# ControlCommande_Motors.net
KiCad netlist of a schematic drawn in Altium Designer
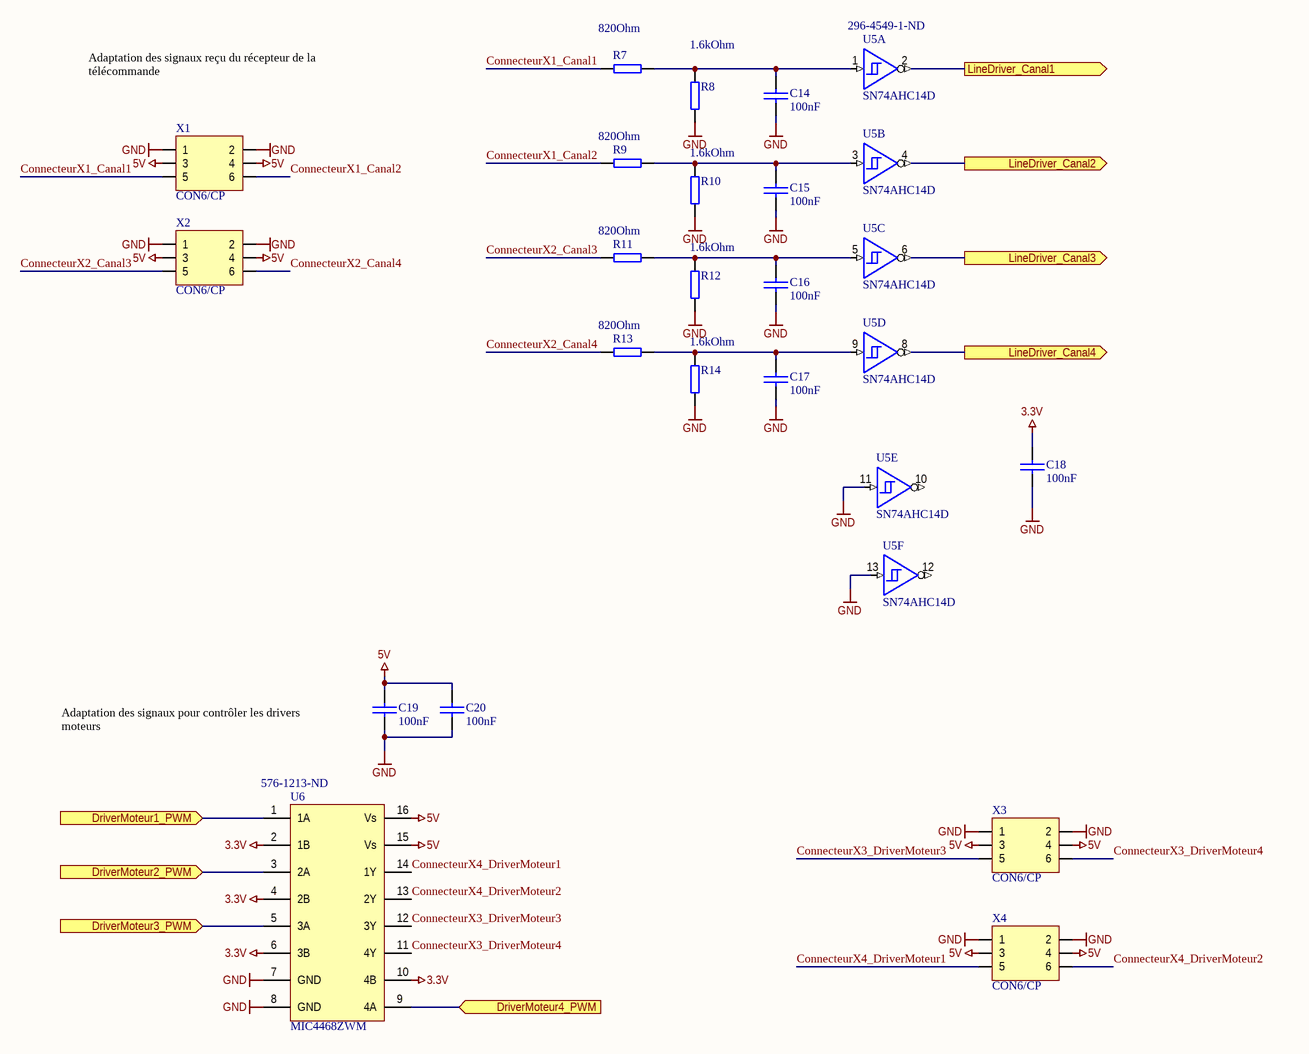
[diagram p0: ControlCommande&Motors.SchDoc]

(export (version "E")
  (design (tool "Eeschema 10.0.6"))
  (components
    (comp (ref "C14")
      (value "100nF")
      (footprint "060301")
      (description "CAPA")
      (fields (field (name "Comment") "GRM188R71E104KA01D"))
      (libsource (lib "General-Sch-205") (part "CAPA"))
    )
    (comp (ref "C15")
      (value "100nF")
      (footprint "060301")
      (description "CAPA")
      (fields (field (name "Comment") "GRM188R71E104KA01D"))
      (libsource (lib "General-Sch-205") (part "CAPA"))
    )
    (comp (ref "C16")
      (value "100nF")
      (footprint "060301")
      (description "CAPA")
      (fields (field (name "Comment") "GRM188R71E104KA01D"))
      (libsource (lib "General-Sch-205") (part "CAPA"))
    )
    (comp (ref "C17")
      (value "100nF")
      (footprint "060301")
      (description "CAPA")
      (fields (field (name "Comment") "GRM188R71E104KA01D"))
      (libsource (lib "General-Sch-205") (part "CAPA"))
    )
    (comp (ref "C18")
      (value "100nF")
      (footprint "060301")
      (description "CAPA")
      (fields (field (name "Comment") "GRM188R71E104KA01D"))
      (libsource (lib "General-Sch-205") (part "CAPA"))
    )
    (comp (ref "C19")
      (value "100nF")
      (footprint "060301")
      (description "CAPA")
      (fields (field (name "Comment") "GRM188R71E104KA01D"))
      (libsource (lib "General-Sch-205") (part "CAPA"))
    )
    (comp (ref "C20")
      (value "100nF")
      (footprint "060301")
      (description "CAPA")
      (fields (field (name "Comment") "GRM188R71E104KA01D"))
      (libsource (lib "General-Sch-205") (part "CAPA"))
    )
    (comp (ref "R7")
      (value "820Ohm")
      (footprint "080501")
      (fields (field (name "Comment") "RMCF0805JT820R"))
      (libsource (lib "General-Sch-205") (part "RES"))
    )
    (comp (ref "R8")
      (value "1.6kOhm")
      (footprint "080501")
      (fields (field (name "Comment") "ERJ-6GEYJ162V"))
      (libsource (lib "General-Sch-205") (part "RES"))
    )
    (comp (ref "R9")
      (value "820Ohm")
      (footprint "080501")
      (fields (field (name "Comment") "RMCF0805JT820R"))
      (libsource (lib "General-Sch-205") (part "RES"))
    )
    (comp (ref "R10")
      (value "1.6kOhm")
      (footprint "080501")
      (fields (field (name "Comment") "ERJ-6GEYJ162V"))
      (libsource (lib "General-Sch-205") (part "RES"))
    )
    (comp (ref "R11")
      (value "820Ohm")
      (footprint "080501")
      (fields (field (name "Comment") "RMCF0805JT820R"))
      (libsource (lib "General-Sch-205") (part "RES"))
    )
    (comp (ref "R12")
      (value "1.6kOhm")
      (footprint "080501")
      (fields (field (name "Comment") "ERJ-6GEYJ162V"))
      (libsource (lib "General-Sch-205") (part "RES"))
    )
    (comp (ref "R13")
      (value "820Ohm")
      (footprint "080501")
      (fields (field (name "Comment") "RMCF0805JT820R"))
      (libsource (lib "General-Sch-205") (part "RES"))
    )
    (comp (ref "R14")
      (value "1.6kOhm")
      (footprint "080501")
      (fields (field (name "Comment") "ERJ-6GEYJ162V"))
      (libsource (lib "General-Sch-205") (part "RES"))
    )
    (comp (ref "U5")
      (value "SN74AHC14D")
      (footprint "SO1401")
      (fields (field (name "SUPPLIER PART NUMBER 1") "296-4549-1-ND"))
      (libsource (lib "EISI") (part "SN74AHC14D"))
    )
    (comp (ref "U6")
      (value "MIC4468ZWM")
      (footprint "SOIC127P1030-16M")
      (fields (field (name "SUPPLIER PART NUMBER 1") "576-1213-ND"))
      (libsource (lib "Schlib1") (part "MIC4468"))
    )
    (comp (ref "X1")
      (value "CON6/CP")
      (footprint "J2X3_2.54")
      (description "Connecteur récepteur télécommande cannaux 1 & 2")
      (libsource (lib "General-Sch-205") (part "CON6/CP"))
    )
    (comp (ref "X2")
      (value "CON6/CP")
      (footprint "J2X3_2.54")
      (description "Connecteur récepteur télécommande cannaux 3 & 4")
      (libsource (lib "General-Sch-205") (part "CON6/CP"))
    )
    (comp (ref "X3")
      (value "CON6/CP")
      (footprint "J2X3_2.54")
      (description "Connecteur contrôleur moteurs 3 (arrière) & 4 (gauche)")
      (libsource (lib "General-Sch-205") (part "CON6/CP"))
    )
    (comp (ref "X4")
      (value "CON6/CP")
      (footprint "J2X3_2.54")
      (description "Connecteur contrôleur moteurs 1 (avant) & 2 (droite)")
      (libsource (lib "General-Sch-205") (part "CON6/CP"))
    )
  )
  (nets
    (net (code "1") (name "/ConnecteurX1_Canal1") (class "Default")
      (node (ref "R7") (pin "1") (pintype "passive"))
      (node (ref "X1") (pin "5") (pinfunction "5_5") (pintype "passive"))
    )
    (net (code "2") (name "/ConnecteurX1_Canal2") (class "Default")
      (node (ref "R9") (pin "1") (pintype "passive"))
      (node (ref "X1") (pin "6") (pinfunction "6_6") (pintype "passive"))
    )
    (net (code "3") (name "/ConnecteurX2_Canal3") (class "Default")
      (node (ref "R11") (pin "1") (pintype "passive"))
      (node (ref "X2") (pin "5") (pinfunction "5_5") (pintype "passive"))
    )
    (net (code "4") (name "/ConnecteurX2_Canal4") (class "Default")
      (node (ref "R13") (pin "1") (pintype "passive"))
      (node (ref "X2") (pin "6") (pinfunction "6_6") (pintype "passive"))
    )
    (net (code "5") (name "/ConnecteurX3_DriverMoteur3") (class "Default")
      (node (ref "U6") (pin "12") (pinfunction "3Y_12") (pintype "passive"))
      (node (ref "X3") (pin "5") (pinfunction "5_5") (pintype "passive"))
    )
    (net (code "6") (name "/ConnecteurX3_DriverMoteur4") (class "Default")
      (node (ref "U6") (pin "11") (pinfunction "4Y_11") (pintype "passive"))
      (node (ref "X3") (pin "6") (pinfunction "6_6") (pintype "passive"))
    )
    (net (code "7") (name "/ConnecteurX4_DriverMoteur1") (class "Default")
      (node (ref "U6") (pin "14") (pinfunction "1Y_14") (pintype "passive"))
      (node (ref "X4") (pin "5") (pinfunction "5_5") (pintype "passive"))
    )
    (net (code "8") (name "/ConnecteurX4_DriverMoteur2") (class "Default")
      (node (ref "U6") (pin "13") (pinfunction "2Y_13") (pintype "passive"))
      (node (ref "X4") (pin "6") (pinfunction "6_6") (pintype "passive"))
    )
    (net (code "9") (name "/DriverMoteur1_PWM") (class "Default")
      (node (ref "U6") (pin "1") (pinfunction "1A_1") (pintype "passive"))
    )
    (net (code "10") (name "/DriverMoteur2_PWM") (class "Default")
      (node (ref "U6") (pin "3") (pinfunction "2A_3") (pintype "passive"))
    )
    (net (code "11") (name "/DriverMoteur3_PWM") (class "Default")
      (node (ref "U6") (pin "5") (pinfunction "3A_5") (pintype "passive"))
    )
    (net (code "12") (name "/DriverMoteur4_PWM") (class "Default")
      (node (ref "U6") (pin "9") (pinfunction "4A_9") (pintype "passive"))
    )
    (net (code "13") (name "/LineDriver_Canal1") (class "Default")
      (node (ref "U5") (pin "2") (pinfunction "2_2") (pintype "output"))
    )
    (net (code "14") (name "/LineDriver_Canal2") (class "Default")
      (node (ref "U5") (pin "4") (pinfunction "4_4") (pintype "output"))
    )
    (net (code "15") (name "/LineDriver_Canal3") (class "Default")
      (node (ref "U5") (pin "6") (pinfunction "6_6") (pintype "output"))
    )
    (net (code "16") (name "/LineDriver_Canal4") (class "Default")
      (node (ref "U5") (pin "8") (pinfunction "8_8") (pintype "output"))
    )
    (net (code "17") (name "3.3V") (class "Default")
      (node (ref "C18") (pin "1") (pintype "passive"))
      (node (ref "U5") (pin "14") (pinfunction "3.3V_14") (pintype "power_in"))
      (node (ref "U6") (pin "10") (pinfunction "4B_10") (pintype "passive"))
      (node (ref "U6") (pin "2") (pinfunction "1B_2") (pintype "passive"))
      (node (ref "U6") (pin "4") (pinfunction "2B_4") (pintype "passive"))
      (node (ref "U6") (pin "6") (pinfunction "3B_6") (pintype "passive"))
    )
    (net (code "18") (name "5V") (class "Default")
      (node (ref "C19") (pin "1") (pintype "passive"))
      (node (ref "C20") (pin "1") (pintype "passive"))
      (node (ref "U6") (pin "15") (pinfunction "Vs_15") (pintype "passive"))
      (node (ref "U6") (pin "16") (pinfunction "Vs_16") (pintype "passive"))
      (node (ref "X1") (pin "3") (pinfunction "3_3") (pintype "passive"))
      (node (ref "X1") (pin "4") (pinfunction "4_4") (pintype "passive"))
      (node (ref "X2") (pin "3") (pinfunction "3_3") (pintype "passive"))
      (node (ref "X2") (pin "4") (pinfunction "4_4") (pintype "passive"))
      (node (ref "X3") (pin "3") (pinfunction "3_3") (pintype "passive"))
      (node (ref "X3") (pin "4") (pinfunction "4_4") (pintype "passive"))
      (node (ref "X4") (pin "3") (pinfunction "3_3") (pintype "passive"))
      (node (ref "X4") (pin "4") (pinfunction "4_4") (pintype "passive"))
    )
    (net (code "19") (name "GND") (class "Default")
      (node (ref "C14") (pin "2") (pintype "passive"))
      (node (ref "C15") (pin "2") (pintype "passive"))
      (node (ref "C16") (pin "2") (pintype "passive"))
      (node (ref "C17") (pin "2") (pintype "passive"))
      (node (ref "C18") (pin "2") (pintype "passive"))
      (node (ref "C19") (pin "2") (pintype "passive"))
      (node (ref "C20") (pin "2") (pintype "passive"))
      (node (ref "R10") (pin "2") (pintype "passive"))
      (node (ref "R12") (pin "2") (pintype "passive"))
      (node (ref "R14") (pin "2") (pintype "passive"))
      (node (ref "R8") (pin "2") (pintype "passive"))
      (node (ref "U5") (pin "11") (pinfunction "11_11") (pintype "input"))
      (node (ref "U5") (pin "13") (pinfunction "13_13") (pintype "input"))
      (node (ref "U5") (pin "7") (pinfunction "GND_7") (pintype "power_in"))
      (node (ref "U6") (pin "7") (pinfunction "GND_7") (pintype "passive"))
      (node (ref "U6") (pin "8") (pinfunction "GND_8") (pintype "passive"))
      (node (ref "X1") (pin "1") (pinfunction "1_1") (pintype "passive"))
      (node (ref "X1") (pin "2") (pinfunction "2_2") (pintype "passive"))
      (node (ref "X2") (pin "1") (pinfunction "1_1") (pintype "passive"))
      (node (ref "X2") (pin "2") (pinfunction "2_2") (pintype "passive"))
      (node (ref "X3") (pin "1") (pinfunction "1_1") (pintype "passive"))
      (node (ref "X3") (pin "2") (pinfunction "2_2") (pintype "passive"))
      (node (ref "X4") (pin "1") (pinfunction "1_1") (pintype "passive"))
      (node (ref "X4") (pin "2") (pinfunction "2_2") (pintype "passive"))
    )
    (net (code "20") (name "Net-(C14-Pad1)") (class "Default")
      (node (ref "C14") (pin "1") (pintype "passive"))
      (node (ref "R7") (pin "2") (pintype "passive"))
      (node (ref "R8") (pin "1") (pintype "passive"))
      (node (ref "U5") (pin "1") (pinfunction "1_1") (pintype "input"))
    )
    (net (code "21") (name "Net-(C15-Pad1)") (class "Default")
      (node (ref "C15") (pin "1") (pintype "passive"))
      (node (ref "R10") (pin "1") (pintype "passive"))
      (node (ref "R9") (pin "2") (pintype "passive"))
      (node (ref "U5") (pin "3") (pinfunction "3_3") (pintype "input"))
    )
    (net (code "22") (name "Net-(C16-Pad1)") (class "Default")
      (node (ref "C16") (pin "1") (pintype "passive"))
      (node (ref "R11") (pin "2") (pintype "passive"))
      (node (ref "R12") (pin "1") (pintype "passive"))
      (node (ref "U5") (pin "5") (pinfunction "5_5") (pintype "input"))
    )
    (net (code "23") (name "Net-(C17-Pad1)") (class "Default")
      (node (ref "C17") (pin "1") (pintype "passive"))
      (node (ref "R13") (pin "2") (pintype "passive"))
      (node (ref "R14") (pin "1") (pintype "passive"))
      (node (ref "U5") (pin "9") (pinfunction "9_9") (pintype "input"))
    )
    (net (code "24") (name "unconnected-(U5-Pad10)") (class "Default")
      (node (ref "U5") (pin "10") (pinfunction "10_10") (pintype "output"))
    )
    (net (code "25") (name "unconnected-(U5-Pad12)") (class "Default")
      (node (ref "U5") (pin "12") (pinfunction "12_12") (pintype "output"))
    )
  )
)
